# frets.net
KiCad netlist of a schematic drawn in EAGLE
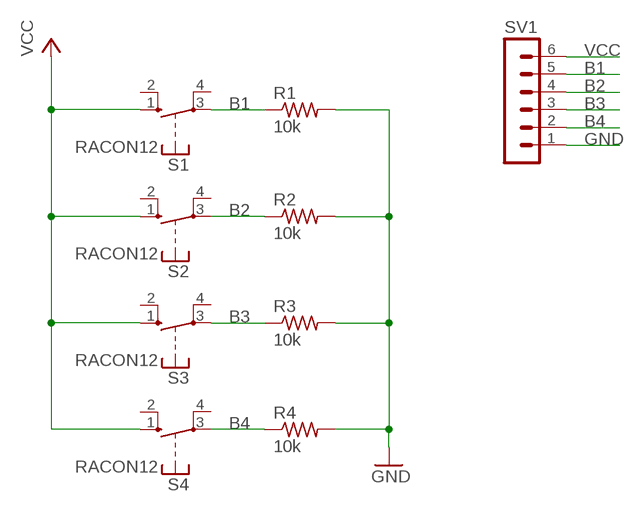
[diagram p0: schematic, sheet 1]

(export (version "E")
  (design (tool "Eeschema 10.0.6"))
  (components
    (comp (ref "R1")
      (value "10k")
      (footprint "eagle-import:0207_7")
      (libsource (lib "eagle-import") (part "R-US_0207/7"))
    )
    (comp (ref "R2")
      (value "10k")
      (footprint "eagle-import:0207_7")
      (libsource (lib "eagle-import") (part "R-US_0207/7"))
    )
    (comp (ref "R3")
      (value "10k")
      (footprint "eagle-import:0207_7")
      (libsource (lib "eagle-import") (part "R-US_0207/7"))
    )
    (comp (ref "R4")
      (value "10k")
      (footprint "eagle-import:0207_7")
      (libsource (lib "eagle-import") (part "R-US_0207/7"))
    )
    (comp (ref "S1")
      (value "RACON12")
      (footprint "eagle-import:RACON12")
      (libsource (lib "eagle-import") (part "RACON12"))
    )
    (comp (ref "S2")
      (value "RACON12")
      (footprint "eagle-import:RACON12")
      (libsource (lib "eagle-import") (part "RACON12"))
    )
    (comp (ref "S3")
      (value "RACON12")
      (footprint "eagle-import:RACON12")
      (libsource (lib "eagle-import") (part "RACON12"))
    )
    (comp (ref "S4")
      (value "RACON12")
      (footprint "eagle-import:RACON12")
      (libsource (lib "eagle-import") (part "RACON12"))
    )
    (comp (ref "SV1")
      (value "MA06-1")
      (footprint "eagle-import:MA06-1")
      (libsource (lib "eagle-import") (part "MA06-1"))
    )
  )
  (nets
    (net (code "1") (name "/B1") (class "Default")
      (node (ref "R1") (pin "1") (pinfunction "1_1") (pintype "passive"))
      (node (ref "S1") (pin "3") (pinfunction "P_3") (pintype "passive"))
      (node (ref "SV1") (pin "5") (pinfunction "5_5") (pintype "passive"))
    )
    (net (code "2") (name "/B2") (class "Default")
      (node (ref "R2") (pin "1") (pinfunction "1_1") (pintype "passive"))
      (node (ref "S2") (pin "3") (pinfunction "P_3") (pintype "passive"))
      (node (ref "SV1") (pin "4") (pinfunction "4_4") (pintype "passive"))
    )
    (net (code "3") (name "/B3") (class "Default")
      (node (ref "R3") (pin "1") (pinfunction "1_1") (pintype "passive"))
      (node (ref "S3") (pin "3") (pinfunction "P_3") (pintype "passive"))
      (node (ref "SV1") (pin "3") (pinfunction "3_3") (pintype "passive"))
    )
    (net (code "4") (name "/B4") (class "Default")
      (node (ref "R4") (pin "1") (pinfunction "1_1") (pintype "passive"))
      (node (ref "S4") (pin "3") (pinfunction "P_3") (pintype "passive"))
      (node (ref "SV1") (pin "2") (pinfunction "2_2") (pintype "passive"))
    )
    (net (code "5") (name "GND") (class "Default")
      (node (ref "R1") (pin "2") (pinfunction "2_2") (pintype "passive"))
      (node (ref "R2") (pin "2") (pinfunction "2_2") (pintype "passive"))
      (node (ref "R3") (pin "2") (pinfunction "2_2") (pintype "passive"))
      (node (ref "R4") (pin "2") (pinfunction "2_2") (pintype "passive"))
      (node (ref "SV1") (pin "1") (pinfunction "1_1") (pintype "passive"))
    )
    (net (code "6") (name "VCC") (class "Default")
      (node (ref "S1") (pin "1") (pinfunction "S_1") (pintype "passive"))
      (node (ref "S2") (pin "1") (pinfunction "S_1") (pintype "passive"))
      (node (ref "S3") (pin "1") (pinfunction "S_1") (pintype "passive"))
      (node (ref "S4") (pin "1") (pinfunction "S_1") (pintype "passive"))
      (node (ref "SV1") (pin "6") (pinfunction "6_6") (pintype "passive"))
    )
    (net (code "7") (name "unconnected-(S1-P-Pad4)") (class "Default")
      (node (ref "S1") (pin "4") (pinfunction "P_4") (pintype "passive"))
    )
    (net (code "8") (name "unconnected-(S1-S-Pad2)") (class "Default")
      (node (ref "S1") (pin "2") (pinfunction "S_2") (pintype "passive"))
    )
    (net (code "9") (name "unconnected-(S2-P-Pad4)") (class "Default")
      (node (ref "S2") (pin "4") (pinfunction "P_4") (pintype "passive"))
    )
    (net (code "10") (name "unconnected-(S2-S-Pad2)") (class "Default")
      (node (ref "S2") (pin "2") (pinfunction "S_2") (pintype "passive"))
    )
    (net (code "11") (name "unconnected-(S3-P-Pad4)") (class "Default")
      (node (ref "S3") (pin "4") (pinfunction "P_4") (pintype "passive"))
    )
    (net (code "12") (name "unconnected-(S3-S-Pad2)") (class "Default")
      (node (ref "S3") (pin "2") (pinfunction "S_2") (pintype "passive"))
    )
    (net (code "13") (name "unconnected-(S4-P-Pad4)") (class "Default")
      (node (ref "S4") (pin "4") (pinfunction "P_4") (pintype "passive"))
    )
    (net (code "14") (name "unconnected-(S4-S-Pad2)") (class "Default")
      (node (ref "S4") (pin "2") (pinfunction "S_2") (pintype "passive"))
    )
  )
)
